# Accelerometer.net
KiCad netlist of a schematic drawn in Altium Designer
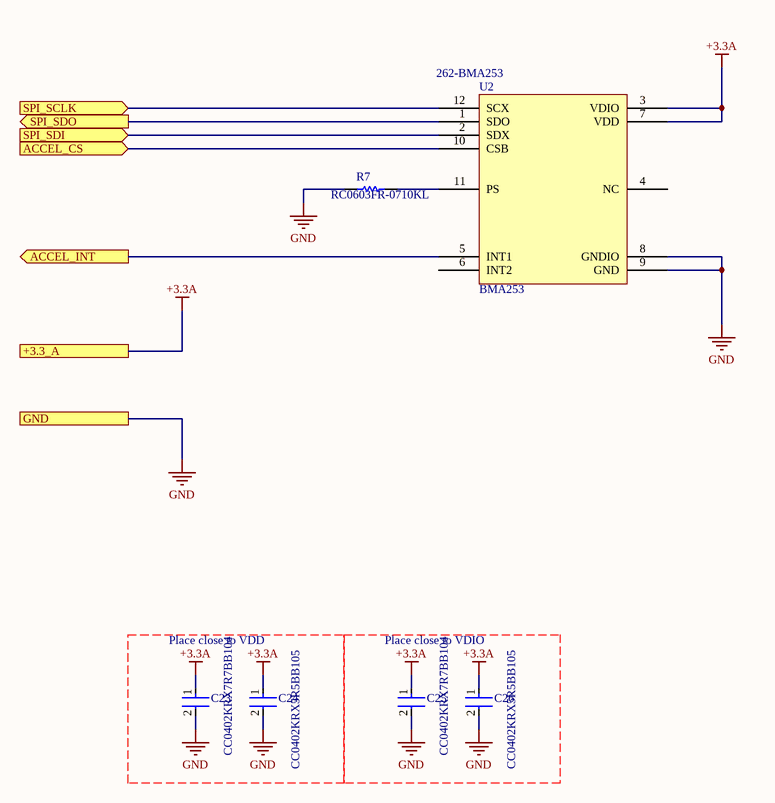
[diagram p0: Accelerometer.SchDoc]

(export (version "E")
  (design (tool "Eeschema 10.0.6"))
  (components
    (comp (ref "C23")
      (value "CC0402KRX7R7BB104")
      (footprint "FP-CC0402-MFG")
      (description "CAP CER 0.1UF 16V X7R 0402")
      (fields (field (name "MANUFACTURER") "YAGEO") (field (name "TOLERANCE") "0.1"))
      (libsource (lib "Altium Content Vault") (part "11868f565c42a9108669ba33697ecf6"))
    )
    (comp (ref "C24")
      (value "CC0402KRX5R5BB105")
      (footprint "FP-CC0402-MFG")
      (description "CAP CER 1UF 6.3V X5R 0402")
      (fields
        (field (name "MANUFACTURER") "YAGEO")
        (field (name "OCTOPART") "https://octopart.com/cc0402krx5r5bb105-yageo-42244618")
      )
      (libsource (lib "Altium Content Vault") (part "11868f565c42a9108669ba33697ecf6"))
    )
    (comp (ref "C25")
      (value "CC0402KRX7R7BB104")
      (footprint "FP-CC0402-MFG")
      (description "CAP CER 0.1UF 16V X7R 0402")
      (fields (field (name "MANUFACTURER") "YAGEO") (field (name "TOLERANCE") "0.1"))
      (libsource (lib "Altium Content Vault") (part "11868f565c42a9108669ba33697ecf6"))
    )
    (comp (ref "C26")
      (value "CC0402KRX5R5BB105")
      (footprint "FP-CC0402-MFG")
      (description "CAP CER 1UF 6.3V X5R 0402")
      (fields
        (field (name "MANUFACTURER") "YAGEO")
        (field (name "OCTOPART") "https://octopart.com/cc0402krx5r5bb105-yageo-42244618")
      )
      (libsource (lib "Altium Content Vault") (part "11868f565c42a9108669ba33697ecf6"))
    )
    (comp (ref "R7")
      (value "RC0603FR-0710KL")
      (footprint "RESC1608X55X25ML10T15")
      (description "Chip Resistor, 10 KOhm, +/- 1%, 01 W, -55 to 155 degC, 0603 (1608 Metric), RoHS, Tape and Reel")
      (fields (field (name "MANUFACTURER") "Yageo") (field (name "TOLERANCE") "1%"))
      (libsource (lib "Altium Content Vault") (part "RES-2"))
    )
    (comp (ref "U2")
      (value "BMA253")
      (footprint "LGA12")
      (fields (field (name "SUPPLIER PART NUMBER 1") "262-BMA253"))
      (libsource (lib "Coin_lib") (part "BMA253"))
    )
  )
  (nets
    (net (code "1") (name "+3.3A") (class "Default")
      (node (ref "C23") (pin "1") (pinfunction "1_1") (pintype "passive"))
      (node (ref "C24") (pin "1") (pinfunction "1_1") (pintype "passive"))
      (node (ref "C25") (pin "1") (pinfunction "1_1") (pintype "passive"))
      (node (ref "C26") (pin "1") (pinfunction "1_1") (pintype "passive"))
      (node (ref "U2") (pin "3") (pinfunction "VDIO_3") (pintype "passive"))
      (node (ref "U2") (pin "7") (pinfunction "VDD_7") (pintype "passive"))
    )
    (net (code "2") (name "/ACCEL_CS") (class "Default")
      (node (ref "U2") (pin "10") (pinfunction "CSB_10") (pintype "passive"))
    )
    (net (code "3") (name "/ACCEL_INT") (class "Default")
      (node (ref "U2") (pin "5") (pinfunction "INT1_5") (pintype "passive"))
    )
    (net (code "4") (name "/SPI_SCLK") (class "Default")
      (node (ref "U2") (pin "12") (pinfunction "SCX_12") (pintype "passive"))
    )
    (net (code "5") (name "/SPI_SDI") (class "Default")
      (node (ref "U2") (pin "2") (pinfunction "SDX_2") (pintype "passive"))
    )
    (net (code "6") (name "/SPI_SDO") (class "Default")
      (node (ref "U2") (pin "1") (pinfunction "SDO_1") (pintype "passive"))
    )
    (net (code "7") (name "GND") (class "Default")
      (node (ref "C23") (pin "2") (pinfunction "2_2") (pintype "passive"))
      (node (ref "C24") (pin "2") (pinfunction "2_2") (pintype "passive"))
      (node (ref "C25") (pin "2") (pinfunction "2_2") (pintype "passive"))
      (node (ref "C26") (pin "2") (pinfunction "2_2") (pintype "passive"))
      (node (ref "R7") (pin "2") (pinfunction "2_2") (pintype "passive"))
      (node (ref "U2") (pin "8") (pinfunction "GNDIO_8") (pintype "passive"))
      (node (ref "U2") (pin "9") (pinfunction "GND_9") (pintype "passive"))
    )
    (net (code "8") (name "Net-(U2-PS)") (class "Default")
      (node (ref "R7") (pin "1") (pinfunction "1_1") (pintype "passive"))
      (node (ref "U2") (pin "11") (pinfunction "PS_11") (pintype "passive"))
    )
    (net (code "9") (name "unconnected-(U2-INT2-Pad6)") (class "Default")
      (node (ref "U2") (pin "6") (pinfunction "INT2_6") (pintype "passive"))
    )
    (net (code "10") (name "unconnected-(U2-NC-Pad4)") (class "Default")
      (node (ref "U2") (pin "4") (pinfunction "NC_4") (pintype "passive"))
    )
  )
)
